# ATSAM3X8E_Main_Controller_-_TR_R1_1.net
KiCad netlist of a schematic drawn in Altium Designer
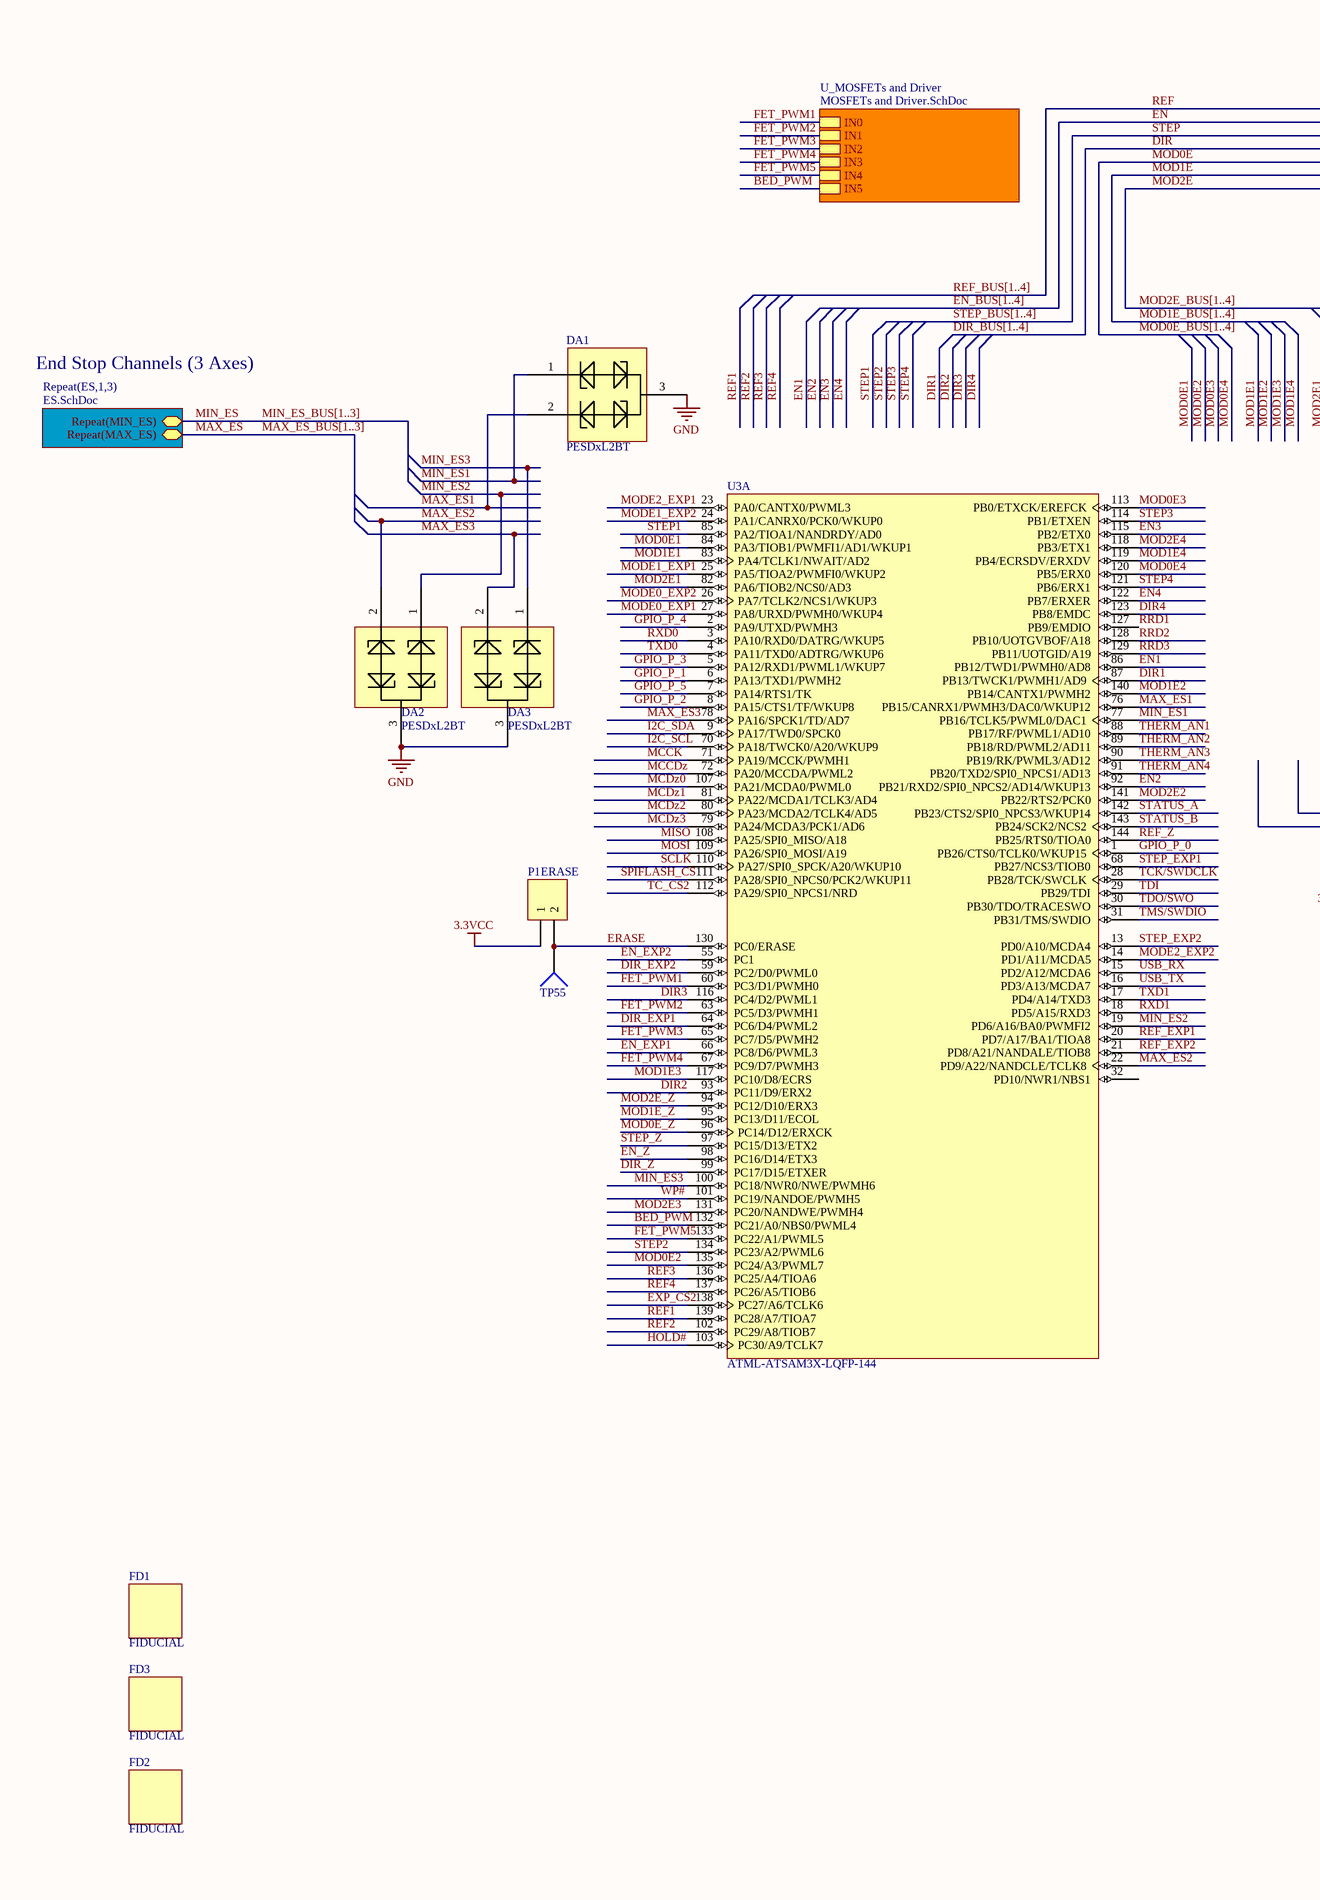
[diagram p0: ATSAM3X8E Main Controller - TR R1.1.SchDoc, left]
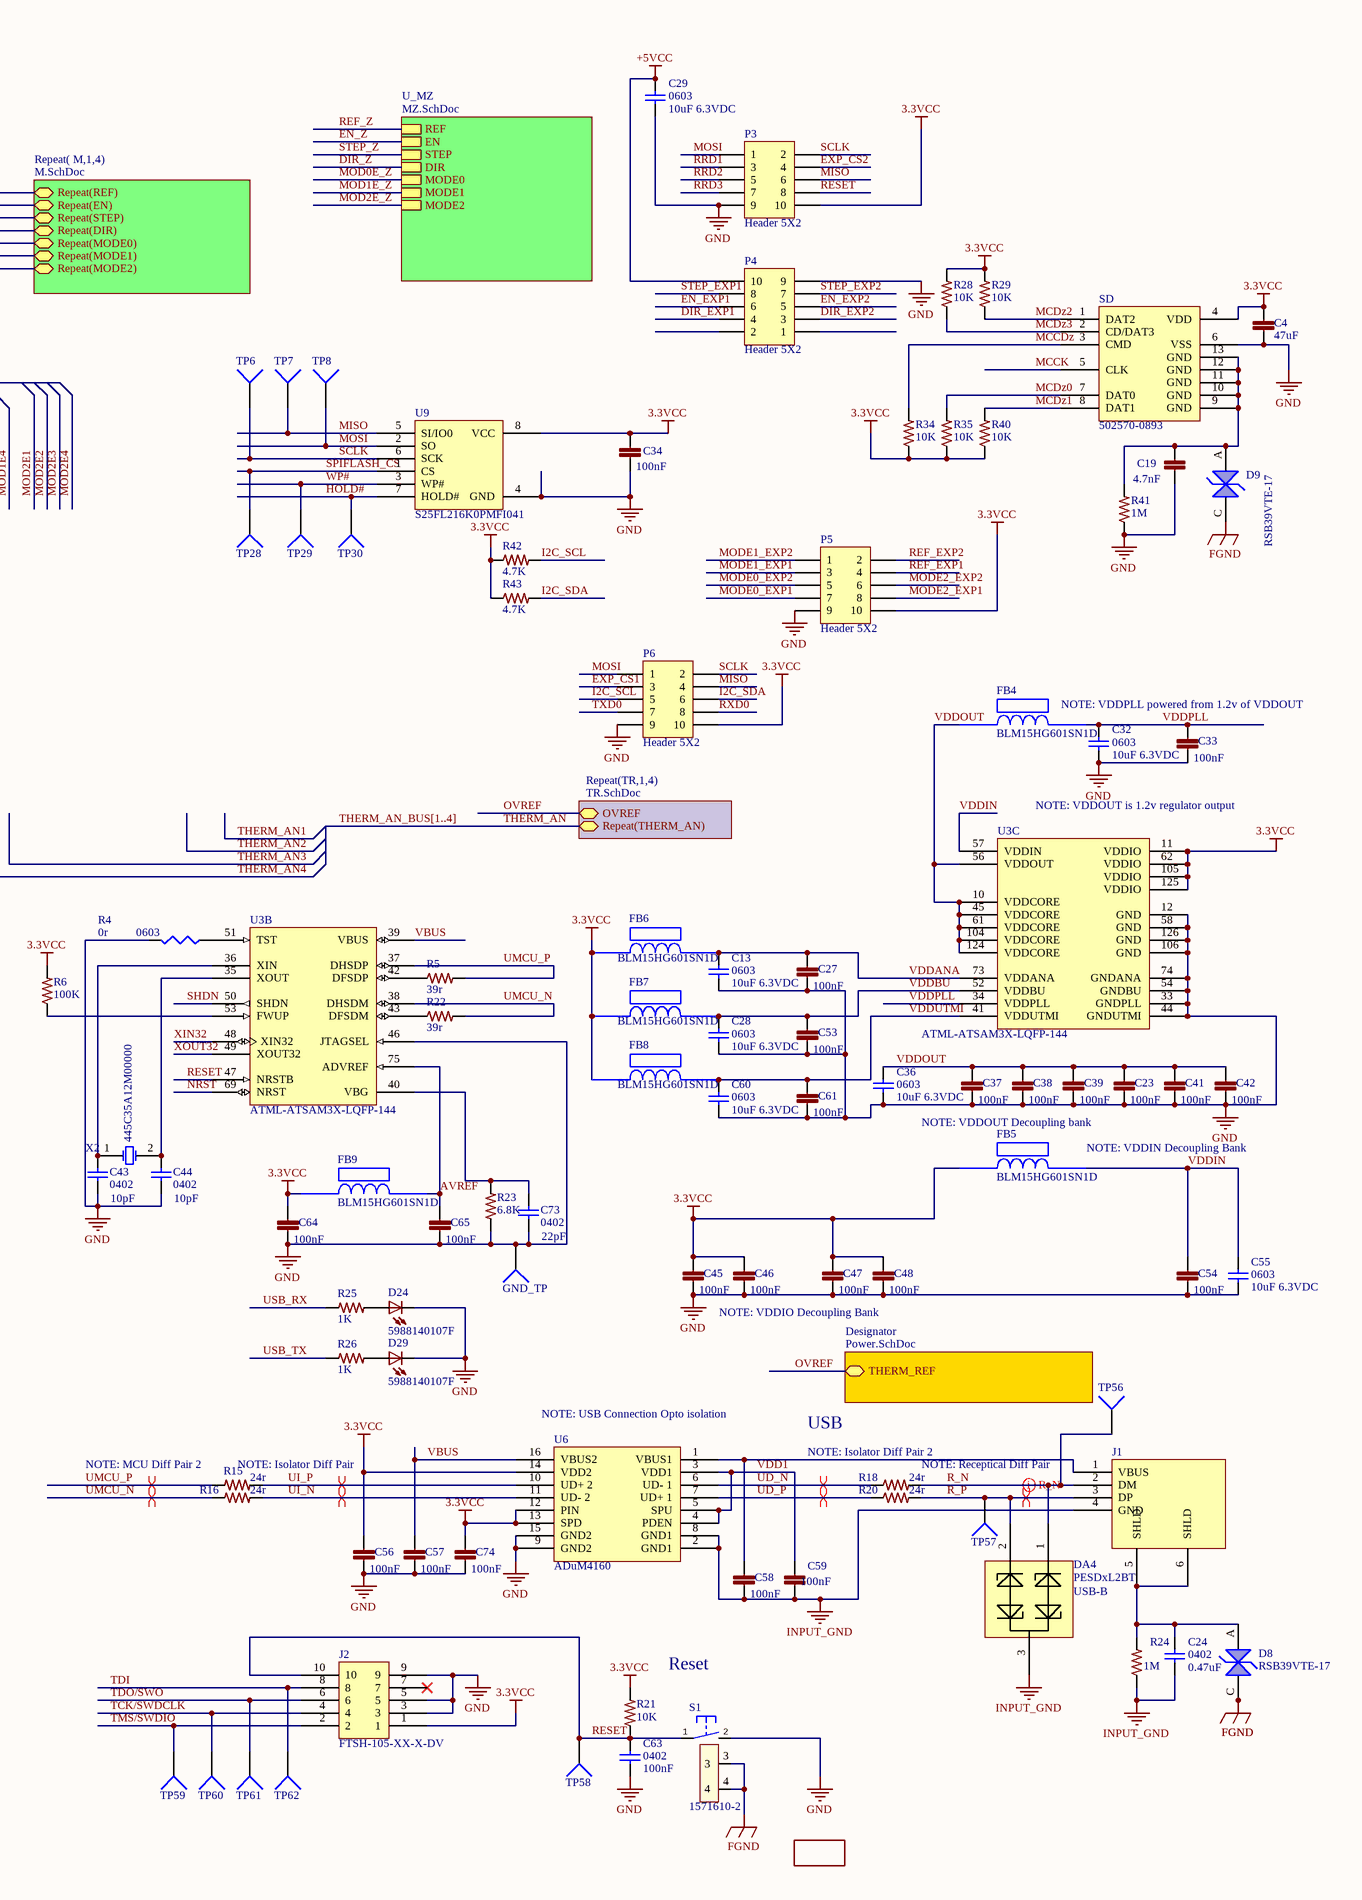
[diagram p1: ATSAM3X8E Main Controller - TR R1.1.SchDoc, right]

(export (version "E")
  (design (tool "Eeschema 10.0.6"))
  (components
    (comp (ref "C4")
      (value "47uF")
      (footprint "C0805")
      (description "CAP CER 47UF 6.3V 20% X5R 0805")
      (fields
        (field (name "MANUFACTURER") "Samsung")
        (field (name "MANUFACTURERPARTNUMBER") "CL21A476MQCLRNC")
        (field (name "PUBLISHER") "UltiMachine")
      )
      (libsource (lib "Tigershark3D") (part "CL21A476MQCLRNC"))
    )
    (comp (ref "C13")
      (value "0603")
      (footprint "C0603")
      (description "CAP CER 10UF 6.3V 10% JB 0603")
      (fields
        (field (name "MFR PART #") "C1608JB0J106K080AB")
        (field (name "MFR") "TDK")
        (field (name "ALTIUM_VALUE") "10uF 6.3VDC")
      )
      (libsource (lib "Tigershark3D") (part "C1608JB0J106K080AB"))
    )
    (comp (ref "C19")
      (value "4.7nF")
      (footprint "C0402")
      (description "CAP CER 0402 4.7nF 25V 10% X7R")
      (fields
        (field (name "MANUFACTURERPARTNUMBER") "CC0402KRX7R8BB472")
        (field (name "PUBLISHER") "UltiMachine")
      )
      (libsource (lib "3Delight") (part "CC0402KRX7R8BB472"))
    )
    (comp (ref "C23")
      (value "100nF")
      (footprint "C0402")
      (description "CAP CER 0402 100nF 16V 10% X7R")
      (fields
        (field (name "MANUFACTURERPARTNUMBER") "GRM155R71C104KA88D")
        (field (name "PUBLISHER") "UltiMachine")
      )
      (libsource (lib "3Delight") (part "GRM155R71C104KA88D"))
    )
    (comp (ref "C24")
      (value "0.47uF")
      (footprint "C0402")
      (description "0.47uF 6.3v C0402 - GRM155R60J474KE19D")
      (fields
        (field (name "MFR PART #") "GRM155R60J474KE19D")
        (field (name "MFR") "Murata")
        (field (name "PACKAGEREFERENCE") "0402")
        (field (name "PUBLISHER") "Ultimachine")
      )
      (libsource (lib "Tigershark3D") (part "GRM155R60J474KE19D"))
    )
    (comp (ref "C27")
      (value "100nF")
      (footprint "C0402")
      (description "CAP CER 0402 100nF 16V 10% X7R")
      (fields
        (field (name "MANUFACTURERPARTNUMBER") "GRM155R71C104KA88D")
        (field (name "PUBLISHER") "UltiMachine")
      )
      (libsource (lib "3Delight") (part "GRM155R71C104KA88D"))
    )
    (comp (ref "C28")
      (value "0603")
      (footprint "C0603")
      (description "CAP CER 10UF 6.3V 10% JB 0603")
      (fields
        (field (name "MFR PART #") "C1608JB0J106K080AB")
        (field (name "MFR") "TDK")
        (field (name "ALTIUM_VALUE") "10uF 6.3VDC")
      )
      (libsource (lib "Tigershark3D") (part "C1608JB0J106K080AB"))
    )
    (comp (ref "C29")
      (value "0603")
      (footprint "C0603")
      (description "CAP CER 10UF 6.3V 10% JB 0603")
      (fields
        (field (name "MFR PART #") "C1608JB0J106K080AB")
        (field (name "MFR") "TDK")
        (field (name "ALTIUM_VALUE") "10uF 6.3VDC")
      )
      (libsource (lib "Tigershark3D") (part "C1608JB0J106K080AB"))
    )
    (comp (ref "C32")
      (value "0603")
      (footprint "C0603")
      (description "CAP CER 10UF 6.3V 10% JB 0603")
      (fields
        (field (name "MFR PART #") "C1608JB0J106K080AB")
        (field (name "MFR") "TDK")
        (field (name "ALTIUM_VALUE") "10uF 6.3VDC")
      )
      (libsource (lib "Tigershark3D") (part "C1608JB0J106K080AB"))
    )
    (comp (ref "C33")
      (value "100nF")
      (footprint "C0402")
      (description "CAP CER 0402 100nF 16V 10% X7R")
      (fields
        (field (name "MANUFACTURERPARTNUMBER") "GRM155R71C104KA88D")
        (field (name "PUBLISHER") "UltiMachine")
      )
      (libsource (lib "3Delight") (part "GRM155R71C104KA88D"))
    )
    (comp (ref "C34")
      (value "100nF")
      (footprint "C0402")
      (description "CAP CER 0402 100nF 16V 10% X7R")
      (fields
        (field (name "MANUFACTURERPARTNUMBER") "GRM155R71C104KA88D")
        (field (name "PUBLISHER") "UltiMachine")
      )
      (libsource (lib "3Delight") (part "GRM155R71C104KA88D"))
    )
    (comp (ref "C36")
      (value "0603")
      (footprint "C0603")
      (description "CAP CER 10UF 6.3V 10% JB 0603")
      (fields
        (field (name "MFR PART #") "C1608JB0J106K080AB")
        (field (name "MFR") "TDK")
        (field (name "ALTIUM_VALUE") "10uF 6.3VDC")
      )
      (libsource (lib "Tigershark3D") (part "C1608JB0J106K080AB"))
    )
    (comp (ref "C37")
      (value "100nF")
      (footprint "C0402")
      (description "CAP CER 0402 100nF 16V 10% X7R")
      (fields
        (field (name "MANUFACTURERPARTNUMBER") "GRM155R71C104KA88D")
        (field (name "PUBLISHER") "UltiMachine")
      )
      (libsource (lib "3Delight") (part "GRM155R71C104KA88D"))
    )
    (comp (ref "C38")
      (value "100nF")
      (footprint "C0402")
      (description "CAP CER 0402 100nF 16V 10% X7R")
      (fields
        (field (name "MANUFACTURERPARTNUMBER") "GRM155R71C104KA88D")
        (field (name "PUBLISHER") "UltiMachine")
      )
      (libsource (lib "3Delight") (part "GRM155R71C104KA88D"))
    )
    (comp (ref "C39")
      (value "100nF")
      (footprint "C0402")
      (description "CAP CER 0402 100nF 16V 10% X7R")
      (fields
        (field (name "MANUFACTURERPARTNUMBER") "GRM155R71C104KA88D")
        (field (name "PUBLISHER") "UltiMachine")
      )
      (libsource (lib "3Delight") (part "GRM155R71C104KA88D"))
    )
    (comp (ref "C41")
      (value "100nF")
      (footprint "C0402")
      (description "CAP CER 0402 100nF 16V 10% X7R")
      (fields
        (field (name "MANUFACTURERPARTNUMBER") "GRM155R71C104KA88D")
        (field (name "PUBLISHER") "UltiMachine")
      )
      (libsource (lib "3Delight") (part "GRM155R71C104KA88D"))
    )
    (comp (ref "C42")
      (value "100nF")
      (footprint "C0402")
      (description "CAP CER 0402 100nF 16V 10% X7R")
      (fields
        (field (name "MANUFACTURERPARTNUMBER") "GRM155R71C104KA88D")
        (field (name "PUBLISHER") "UltiMachine")
      )
      (libsource (lib "3Delight") (part "GRM155R71C104KA88D"))
    )
    (comp (ref "C43")
      (value "0402")
      (footprint "C0402")
      (description "CAP CER 10PF 50V 5% NP0 0402")
      (fields
        (field (name "MFR PART #") "CL05C100JB5NNNC")
        (field (name "MFR") "Samsung")
        (field (name "ALTIUM_VALUE") "10pF")
        (field (name "PUBLISHER") "Ultimachine")
      )
      (libsource (lib "Tigershark3D") (part "CL05C100JB5NNNC"))
    )
    (comp (ref "C44")
      (value "0402")
      (footprint "C0402")
      (description "CAP CER 10PF 50V 5% NP0 0402")
      (fields
        (field (name "MFR PART #") "CL05C100JB5NNNC")
        (field (name "MFR") "Samsung")
        (field (name "ALTIUM_VALUE") "10pF")
        (field (name "PUBLISHER") "Ultimachine")
      )
      (libsource (lib "Tigershark3D") (part "CL05C100JB5NNNC"))
    )
    (comp (ref "C45")
      (value "100nF")
      (footprint "C0402")
      (description "CAP CER 0402 100nF 16V 10% X7R")
      (fields
        (field (name "MANUFACTURERPARTNUMBER") "GRM155R71C104KA88D")
        (field (name "PUBLISHER") "UltiMachine")
      )
      (libsource (lib "3Delight") (part "GRM155R71C104KA88D"))
    )
    (comp (ref "C46")
      (value "100nF")
      (footprint "C0402")
      (description "CAP CER 0402 100nF 16V 10% X7R")
      (fields
        (field (name "MANUFACTURERPARTNUMBER") "GRM155R71C104KA88D")
        (field (name "PUBLISHER") "UltiMachine")
      )
      (libsource (lib "3Delight") (part "GRM155R71C104KA88D"))
    )
    (comp (ref "C47")
      (value "100nF")
      (footprint "C0402")
      (description "CAP CER 0402 100nF 16V 10% X7R")
      (fields
        (field (name "MANUFACTURERPARTNUMBER") "GRM155R71C104KA88D")
        (field (name "PUBLISHER") "UltiMachine")
      )
      (libsource (lib "3Delight") (part "GRM155R71C104KA88D"))
    )
    (comp (ref "C48")
      (value "100nF")
      (footprint "C0402")
      (description "CAP CER 0402 100nF 16V 10% X7R")
      (fields
        (field (name "MANUFACTURERPARTNUMBER") "GRM155R71C104KA88D")
        (field (name "PUBLISHER") "UltiMachine")
      )
      (libsource (lib "3Delight") (part "GRM155R71C104KA88D"))
    )
    (comp (ref "C53")
      (value "100nF")
      (footprint "C0402")
      (description "CAP CER 0402 100nF 16V 10% X7R")
      (fields
        (field (name "MANUFACTURERPARTNUMBER") "GRM155R71C104KA88D")
        (field (name "PUBLISHER") "UltiMachine")
      )
      (libsource (lib "3Delight") (part "GRM155R71C104KA88D"))
    )
    (comp (ref "C54")
      (value "100nF")
      (footprint "C0402")
      (description "CAP CER 0402 100nF 16V 10% X7R")
      (fields
        (field (name "MANUFACTURERPARTNUMBER") "GRM155R71C104KA88D")
        (field (name "PUBLISHER") "UltiMachine")
      )
      (libsource (lib "3Delight") (part "GRM155R71C104KA88D"))
    )
    (comp (ref "C55")
      (value "0603")
      (footprint "C0603")
      (description "CAP CER 10UF 6.3V 10% JB 0603")
      (fields
        (field (name "MFR PART #") "C1608JB0J106K080AB")
        (field (name "MFR") "TDK")
        (field (name "ALTIUM_VALUE") "10uF 6.3VDC")
      )
      (libsource (lib "Tigershark3D") (part "C1608JB0J106K080AB"))
    )
    (comp (ref "C56")
      (value "100nF")
      (footprint "C0402")
      (description "CAP CER 0402 100nF 16V 10% X7R")
      (fields
        (field (name "MANUFACTURERPARTNUMBER") "GRM155R71C104KA88D")
        (field (name "PUBLISHER") "UltiMachine")
      )
      (libsource (lib "3Delight") (part "GRM155R71C104KA88D"))
    )
    (comp (ref "C57")
      (value "100nF")
      (footprint "C0402")
      (description "CAP CER 0402 100nF 16V 10% X7R")
      (fields
        (field (name "MANUFACTURERPARTNUMBER") "GRM155R71C104KA88D")
        (field (name "PUBLISHER") "UltiMachine")
      )
      (libsource (lib "3Delight") (part "GRM155R71C104KA88D"))
    )
    (comp (ref "C58")
      (value "100nF")
      (footprint "C0402")
      (description "CAP CER 0402 100nF 16V 10% X7R")
      (fields
        (field (name "MANUFACTURERPARTNUMBER") "GRM155R71C104KA88D")
        (field (name "PUBLISHER") "UltiMachine")
      )
      (libsource (lib "3Delight") (part "GRM155R71C104KA88D"))
    )
    (comp (ref "C59")
      (value "100nF")
      (footprint "C0402")
      (description "CAP CER 0402 100nF 16V 10% X7R")
      (fields
        (field (name "MANUFACTURERPARTNUMBER") "GRM155R71C104KA88D")
        (field (name "PUBLISHER") "UltiMachine")
      )
      (libsource (lib "3Delight") (part "GRM155R71C104KA88D"))
    )
    (comp (ref "C60")
      (value "0603")
      (footprint "C0603")
      (description "CAP CER 10UF 6.3V 10% JB 0603")
      (fields
        (field (name "MFR PART #") "C1608JB0J106K080AB")
        (field (name "MFR") "TDK")
        (field (name "ALTIUM_VALUE") "10uF 6.3VDC")
      )
      (libsource (lib "Tigershark3D") (part "C1608JB0J106K080AB"))
    )
    (comp (ref "C61")
      (value "100nF")
      (footprint "C0402")
      (description "CAP CER 0402 100nF 16V 10% X7R")
      (fields
        (field (name "MANUFACTURERPARTNUMBER") "GRM155R71C104KA88D")
        (field (name "PUBLISHER") "UltiMachine")
      )
      (libsource (lib "3Delight") (part "GRM155R71C104KA88D"))
    )
    (comp (ref "C63")
      (value "100nF")
      (footprint "C0402")
      (description "Capacitor (Semiconductor SIM Model)")
      (fields
        (field (name "MFR PART #") "GRM155R71C104KA88D")
        (field (name "MFR") "Murata")
        (field (name "PACKAGEREFERENCE") "0402")
        (field (name "PUBLISHER") "Ultimachine")
      )
      (libsource (lib "Tigershark3D") (part "100nF C0402 - GRM155R71C104KA88D"))
    )
    (comp (ref "C64")
      (value "100nF")
      (footprint "C0402")
      (description "CAP CER 0402 100nF 16V 10% X7R")
      (fields
        (field (name "MANUFACTURERPARTNUMBER") "GRM155R71C104KA88D")
        (field (name "PUBLISHER") "UltiMachine")
      )
      (libsource (lib "3Delight") (part "GRM155R71C104KA88D"))
    )
    (comp (ref "C65")
      (value "100nF")
      (footprint "C0402")
      (description "CAP CER 0402 100nF 16V 10% X7R")
      (fields
        (field (name "MANUFACTURERPARTNUMBER") "GRM155R71C104KA88D")
        (field (name "PUBLISHER") "UltiMachine")
      )
      (libsource (lib "3Delight") (part "GRM155R71C104KA88D"))
    )
    (comp (ref "C73")
      (value "0402")
      (footprint "C0402")
      (description "CAP CER 22PF 50V 5% NP0 0402")
      (fields
        (field (name "MFR PART #") "CL05C220JB5NNNC")
        (field (name "MFR") "Samsung")
        (field (name "ALTIUM_VALUE") "22pF")
        (field (name "PUBLISHER") "Ultimachine")
      )
      (libsource (lib "Tigershark3D") (part "CL05C220JB5NNNC"))
    )
    (comp (ref "C74")
      (value "100nF")
      (footprint "C0402")
      (description "CAP CER 0402 100nF 16V 10% X7R")
      (fields
        (field (name "MANUFACTURERPARTNUMBER") "GRM155R71C104KA88D")
        (field (name "PUBLISHER") "UltiMachine")
      )
      (libsource (lib "3Delight") (part "GRM155R71C104KA88D"))
    )
    (comp (ref "D8")
      (value "RSB39VTE-17")
      (footprint "SOD323-R")
      (description "DIODE TVS")
      (libsource (lib "Tigershark3D") (part "RSB39VTE-17"))
    )
    (comp (ref "D9")
      (value "RSB39VTE-17")
      (footprint "SOD323-R")
      (description "DIODE TVS")
      (libsource (lib "3Delight") (part "RSB39VTE-17"))
    )
    (comp (ref "D24")
      (value "5988140107F")
      (footprint "LED2012120")
      (description "LED 0805 Yellow")
      (fields (field (name "PUBLISHER") "UltiMachine"))
      (libsource (lib "Tigershark3D") (part "5988140107F"))
    )
    (comp (ref "D29")
      (value "5988140107F")
      (footprint "LED2012120")
      (description "LED 0805 Yellow")
      (fields (field (name "PUBLISHER") "UltiMachine"))
      (libsource (lib "Tigershark3D") (part "5988140107F"))
    )
    (comp (ref "DA1")
      (value "PESDxL2BT")
      (footprint "SOT95P230X110-3N")
      (description "PESDxL2BT TVS Diode Array 2x")
      (libsource (lib "") (part "PESDxL2BT_1"))
    )
    (comp (ref "DA2")
      (value "PESDxL2BT")
      (footprint "SOT95P230X110-3N")
      (description "PESDxL2BT TVS Diode Array 2x")
      (libsource (lib "ZMBo Schematic Library") (part "PESDxL2BT"))
    )
    (comp (ref "DA3")
      (value "PESDxL2BT")
      (footprint "SOT95P230X110-3N")
      (description "PESDxL2BT TVS Diode Array 2x")
      (libsource (lib "ZMBo Schematic Library") (part "PESDxL2BT"))
    )
    (comp (ref "DA4")
      (value "PESDxL2BT")
      (footprint "SOT95P230X110-3N")
      (description "PESDxL2BT TVS Diode Array 2x")
      (libsource (lib "ZMBo Schematic Library") (part "PESDxL2BT"))
    )
    (comp (ref "FB4")
      (value "BLM15HG601SN1D")
      (footprint "BLM18PG121SN1D")
      (libsource (lib "AHD Part Library") (part "BLM15HG601SN1D"))
    )
    (comp (ref "FB5")
      (value "BLM15HG601SN1D")
      (footprint "BLM18PG121SN1D")
      (libsource (lib "AHD Part Library") (part "BLM15HG601SN1D"))
    )
    (comp (ref "FB6")
      (value "BLM15HG601SN1D")
      (footprint "BLM18PG121SN1D")
      (libsource (lib "AHD Part Library") (part "BLM15HG601SN1D"))
    )
    (comp (ref "FB7")
      (value "BLM15HG601SN1D")
      (footprint "BLM18PG121SN1D")
      (libsource (lib "AHD Part Library") (part "BLM15HG601SN1D"))
    )
    (comp (ref "FB8")
      (value "BLM15HG601SN1D")
      (footprint "BLM18PG121SN1D")
      (libsource (lib "AHD Part Library") (part "BLM15HG601SN1D"))
    )
    (comp (ref "FB9")
      (value "BLM15HG601SN1D")
      (footprint "BLM18PG121SN1D")
      (libsource (lib "AHD Part Library") (part "BLM15HG601SN1D"))
    )
    (comp (ref "FD1")
      (value "FIDUCIAL")
      (footprint "FIDUCIAL-1X2")
      (libsource (lib "ZMBo Schematic Library") (part "FIDUCIAL"))
    )
    (comp (ref "FD2")
      (value "FIDUCIAL")
      (footprint "FIDUCIAL-1X2")
      (libsource (lib "ZMBo Schematic Library") (part "FIDUCIAL"))
    )
    (comp (ref "FD3")
      (value "FIDUCIAL")
      (footprint "FIDUCIAL-1X2")
      (libsource (lib "ZMBo Schematic Library") (part "FIDUCIAL"))
    )
    (comp (ref "GND_TP")
      (value "TP4")
      (footprint "TP-2")
      (description "Socket")
      (fields (field (name "PUBLISHER") "Altium Limited"))
      (libsource (lib "ZMBo Schematic Library") (part "Socket"))
    )
    (comp (ref "J1")
      (value "USB-B")
      (footprint "PN61729")
      (libsource (lib "ZMBo Schematic Library") (part "USB-B"))
    )
    (comp (ref "J2")
      (value "FTSH-105-XX-X-DV")
      (footprint "FTSH-105-XX-X-DV")
      (libsource (lib "Adams Altium Library") (part "ARM Cortex JTAG-DEBUG Header"))
    )
    (comp (ref "LOGO1")
      (value "OSHW_LOGO_8MILX0150-NT")
      (footprint "OSHW_8X150_NOTEXT")
      (fields (field (name "PUBLISHER") "UltiMachine"))
      (libsource (lib "3Delight") (part "OSHW_LOGO_8MILX0150-NT"))
    )
    (comp (ref "P1")
      (value "ERASE")
      (footprint "HDR1X2")
      (description "Header, 2-Pin")
      (fields (field (name "PUBLISHER") "Altium Limited"))
      (libsource (lib "Miscellaneous Connectors") (part "Header 2"))
    )
    (comp (ref "P3")
      (value "Header 5X2")
      (footprint "HDR2X5")
      (description "Header, 5-Pin, Dual row")
      (fields (field (name "PUBLISHER") "Altium Limited"))
      (libsource (lib "Miscellaneous Connectors") (part "Header 5X2"))
    )
    (comp (ref "P4")
      (value "Header 5X2")
      (footprint "HDR2X5")
      (description "Header, 5-Pin, Dual row")
      (fields (field (name "PUBLISHER") "Altium Limited"))
      (libsource (lib "") (part "Header 5X2_1"))
    )
    (comp (ref "P5")
      (value "Header 5X2")
      (footprint "HDR2X5")
      (description "Header, 5-Pin, Dual row")
      (fields (field (name "PUBLISHER") "Altium Limited"))
      (libsource (lib "Miscellaneous Connectors") (part "Header 5X2"))
    )
    (comp (ref "P6")
      (value "Header 5X2")
      (footprint "HDR2X5")
      (description "Header, 5-Pin, Dual row")
      (fields (field (name "PUBLISHER") "Altium Limited"))
      (libsource (lib "Miscellaneous Connectors") (part "Header 5X2"))
    )
    (comp (ref "R4")
      (value "0603")
      (footprint "J1-0603")
      (description "Resistor")
      (fields (field (name "ALTIUM_VALUE") "0r") (field (name "PUBLISHER") "Altium Limited"))
      (libsource (lib "Miscellaneous Devices") (part "Res3"))
    )
    (comp (ref "R5")
      (value "39r")
      (footprint "R0402")
      (description "RES SMD 39 OHM 1% 1/10W 0402")
      (fields
        (field (name "MANUFACTURER") "Panasonic")
        (field (name "MANUFACTURERPARTNUMBER") "ERJ-2RKF39R0X")
        (field (name "PUBLISHER") "UltiMachine")
      )
      (libsource (lib "Tigershark3D") (part "ERJ-2RKF39R0X"))
    )
    (comp (ref "R6")
      (value "100K")
      (footprint "R0603")
      (description "RES 100K OHM 1/10W 1% 0603 SMD")
      (fields
        (field (name "MANUFACTURERPARTNUMBER") "RC0603FR-07100KL")
        (field (name "PUBLISHER") "UltiMachine")
      )
      (libsource (lib "Tigershark3D") (part "RC0603FR-07100KL"))
    )
    (comp (ref "R15")
      (value "24r")
      (footprint "R0603")
      (description "RES SMD 24 OHM 1% 1/10W 0603")
      (fields
        (field (name "MANUFACTURER") "Samsung")
        (field (name "MANUFACTURERPARTNUMBER") "RC0603FR-07100KL")
        (field (name "PUBLISHER") "UltiMachine")
      )
      (libsource (lib "Tigershark3D") (part "RC1608F240CS"))
    )
    (comp (ref "R16")
      (value "24r")
      (footprint "R0603")
      (description "RES SMD 24 OHM 1% 1/10W 0603")
      (fields
        (field (name "MANUFACTURER") "Samsung")
        (field (name "MANUFACTURERPARTNUMBER") "RC0603FR-07100KL")
        (field (name "PUBLISHER") "UltiMachine")
      )
      (libsource (lib "Tigershark3D") (part "RC1608F240CS"))
    )
    (comp (ref "R18")
      (value "24r")
      (footprint "R0603")
      (description "RES SMD 24 OHM 1% 1/10W 0603")
      (fields
        (field (name "MANUFACTURER") "Samsung")
        (field (name "MANUFACTURERPARTNUMBER") "RC0603FR-07100KL")
        (field (name "PUBLISHER") "UltiMachine")
      )
      (libsource (lib "Tigershark3D") (part "RC1608F240CS"))
    )
    (comp (ref "R20")
      (value "24r")
      (footprint "R0603")
      (description "RES SMD 24 OHM 1% 1/10W 0603")
      (fields
        (field (name "MANUFACTURER") "Samsung")
        (field (name "MANUFACTURERPARTNUMBER") "RC0603FR-07100KL")
        (field (name "PUBLISHER") "UltiMachine")
      )
      (libsource (lib "Tigershark3D") (part "RC1608F240CS"))
    )
    (comp (ref "R21")
      (value "10K")
      (footprint "R0603")
      (description "RES 0603 10K 100mW 1%")
      (fields
        (field (name "MANUFACTURERPARTNUMBER") "ERJ-3EKF1002V")
        (field (name "PUBLISHER") "UltiMachine")
      )
      (libsource (lib "3Delight") (part "ERJ-3EKF1002V"))
    )
    (comp (ref "R22")
      (value "39r")
      (footprint "R0402")
      (description "RES SMD 39 OHM 1% 1/10W 0402")
      (fields
        (field (name "MANUFACTURER") "Panasonic")
        (field (name "MANUFACTURERPARTNUMBER") "ERJ-2RKF39R0X")
        (field (name "PUBLISHER") "UltiMachine")
      )
      (libsource (lib "Tigershark3D") (part "ERJ-2RKF39R0X"))
    )
    (comp (ref "R23")
      (value "6.8K")
      (footprint "R0402")
      (description "RES SMD 6.8K OHM 1% 1/16W 0402")
      (fields
        (field (name "MANUFACTURER") "Vishay Dale")
        (field (name "MANUFACTURERPARTNUMBER") "CRCW04026K80FKED")
        (field (name "PUBLISHER") "UltiMachine")
      )
      (libsource (lib "Tigershark3D") (part "CRCW04026K80FKED"))
    )
    (comp (ref "R24")
      (value "1M")
      (footprint "R0402")
      (description "RES 0402 1M 100mW 5%")
      (fields (field (name "MANUFACTURERPARTNUMBER") "ERJ2GEJ105X") (field (name "PUBLISHER") "UltiMachine"))
      (libsource (lib "Tigershark3D") (part "ERJ2GEJ105X"))
    )
    (comp (ref "R25")
      (value "1K")
      (footprint "R0603")
      (description "RES 0603 1K 100mW 1%")
      (fields
        (field (name "MANUFACTURERPARTNUMBER") "ERJ-3EKF1001V")
        (field (name "PUBLISHER") "UltiMachine")
      )
      (libsource (lib "Tigershark3D") (part "ERJ-3EKF1001V"))
    )
    (comp (ref "R26")
      (value "1K")
      (footprint "R0603")
      (description "RES 0603 1K 100mW 1%")
      (fields
        (field (name "MANUFACTURERPARTNUMBER") "ERJ-3EKF1001V")
        (field (name "PUBLISHER") "UltiMachine")
      )
      (libsource (lib "Tigershark3D") (part "ERJ-3EKF1001V"))
    )
    (comp (ref "R28")
      (value "10K")
      (footprint "R0603")
      (description "RES 0603 10K 100mW 1%")
      (fields
        (field (name "MANUFACTURERPARTNUMBER") "ERJ-3EKF1002V")
        (field (name "PUBLISHER") "UltiMachine")
      )
      (libsource (lib "Tigershark3D") (part "ERJ-3EKF1002V"))
    )
    (comp (ref "R29")
      (value "10K")
      (footprint "R0603")
      (description "RES 0603 10K 100mW 1%")
      (fields
        (field (name "MANUFACTURERPARTNUMBER") "ERJ-3EKF1002V")
        (field (name "PUBLISHER") "UltiMachine")
      )
      (libsource (lib "Tigershark3D") (part "ERJ-3EKF1002V"))
    )
    (comp (ref "R34")
      (value "10K")
      (footprint "R0603")
      (description "RES 0603 10K 100mW 1%")
      (fields
        (field (name "MANUFACTURERPARTNUMBER") "ERJ-3EKF1002V")
        (field (name "PUBLISHER") "UltiMachine")
      )
      (libsource (lib "Tigershark3D") (part "ERJ-3EKF1002V"))
    )
    (comp (ref "R35")
      (value "10K")
      (footprint "R0603")
      (description "RES 0603 10K 100mW 1%")
      (fields
        (field (name "MANUFACTURERPARTNUMBER") "ERJ-3EKF1002V")
        (field (name "PUBLISHER") "UltiMachine")
      )
      (libsource (lib "Tigershark3D") (part "ERJ-3EKF1002V"))
    )
    (comp (ref "R40")
      (value "10K")
      (footprint "R0603")
      (description "RES 0603 10K 100mW 1%")
      (fields
        (field (name "MANUFACTURERPARTNUMBER") "ERJ-3EKF1002V")
        (field (name "PUBLISHER") "UltiMachine")
      )
      (libsource (lib "Tigershark3D") (part "ERJ-3EKF1002V"))
    )
    (comp (ref "R41")
      (value "1M")
      (footprint "R0402")
      (description "RES 0402 1M 100mW 5%")
      (fields (field (name "MANUFACTURERPARTNUMBER") "ERJ2GEJ105X") (field (name "PUBLISHER") "UltiMachine"))
      (libsource (lib "3Delight") (part "ERJ2GEJ105X"))
    )
    (comp (ref "R42")
      (value "4.7K")
      (footprint "R0603")
      (description "RES 0603 4.7K 100mW 1%")
      (fields (field (name "MANUFACTURERPARTNUMBER") "ERJ3EKF4701V") (field (name "PUBLISHER") "UltiMachine"))
      (libsource (lib "Tigershark3D") (part "ERJ3EKF4701V"))
    )
    (comp (ref "R43")
      (value "4.7K")
      (footprint "R0603")
      (description "RES 0603 4.7K 100mW 1%")
      (fields (field (name "MANUFACTURERPARTNUMBER") "ERJ3EKF4701V") (field (name "PUBLISHER") "UltiMachine"))
      (libsource (lib "Tigershark3D") (part "ERJ3EKF4701V"))
    )
    (comp (ref "S1")
      (value "1571610-2")
      (footprint "B3F-31XX")
      (description "SWTCH Momentary Washable")
      (fields
        (field (name "MANUFACTURER") "Omron")
        (field (name "MANUFACTURER_1") "TE")
        (field (name "PUBLISHER") "UltiMachine")
      )
      (libsource (lib "ZMBo Schematic Library") (part "1571610-2_1"))
    )
    (comp (ref "SD")
      (value "502570-0893")
      (footprint "502570-0893 - Molex SD")
      (description "microSD 502570-0893 Molex Part")
      (libsource (lib "Tigershark3D") (part "502570-0893"))
    )
    (comp (ref "TP6")
      (value "TP4")
      (footprint "TP-2")
      (description "Socket")
      (fields (field (name "PUBLISHER") "Altium Limited"))
      (libsource (lib "ZMBo Schematic Library") (part "Socket"))
    )
    (comp (ref "TP7")
      (value "TP4")
      (footprint "TP-2")
      (description "Socket")
      (fields (field (name "PUBLISHER") "Altium Limited"))
      (libsource (lib "ZMBo Schematic Library") (part "Socket"))
    )
    (comp (ref "TP8")
      (value "TP4")
      (footprint "TP-2")
      (description "Socket")
      (fields (field (name "PUBLISHER") "Altium Limited"))
      (libsource (lib "ZMBo Schematic Library") (part "Socket"))
    )
    (comp (ref "TP28")
      (value "TP4")
      (footprint "TP-2")
      (description "Socket")
      (fields (field (name "PUBLISHER") "Altium Limited"))
      (libsource (lib "ZMBo Schematic Library") (part "Socket"))
    )
    (comp (ref "TP29")
      (value "TP4")
      (footprint "TP-2")
      (description "Socket")
      (fields (field (name "PUBLISHER") "Altium Limited"))
      (libsource (lib "ZMBo Schematic Library") (part "Socket"))
    )
    (comp (ref "TP30")
      (value "TP4")
      (footprint "TP-2")
      (description "Socket")
      (fields (field (name "PUBLISHER") "Altium Limited"))
      (libsource (lib "ZMBo Schematic Library") (part "Socket"))
    )
    (comp (ref "TP55")
      (value "TP4")
      (footprint "TP-2")
      (description "Socket")
      (fields (field (name "PUBLISHER") "Altium Limited"))
      (libsource (lib "ZMBo Schematic Library") (part "Socket"))
    )
    (comp (ref "TP56")
      (value "TP4")
      (footprint "TP-2")
      (description "Socket")
      (fields (field (name "PUBLISHER") "Altium Limited"))
      (libsource (lib "ZMBo Schematic Library") (part "Socket"))
    )
    (comp (ref "TP57")
      (value "TP4")
      (footprint "TP-2")
      (description "Socket")
      (fields (field (name "PUBLISHER") "Altium Limited"))
      (libsource (lib "ZMBo Schematic Library") (part "Socket"))
    )
    (comp (ref "TP58")
      (value "TP4")
      (footprint "TP-2")
      (description "Socket")
      (fields (field (name "PUBLISHER") "Altium Limited"))
      (libsource (lib "ZMBo Schematic Library") (part "Socket"))
    )
    (comp (ref "TP59")
      (value "TP4")
      (footprint "TP-2")
      (description "Socket")
      (fields (field (name "PUBLISHER") "Altium Limited"))
      (libsource (lib "ZMBo Schematic Library") (part "Socket"))
    )
    (comp (ref "TP60")
      (value "TP4")
      (footprint "TP-2")
      (description "Socket")
      (fields (field (name "PUBLISHER") "Altium Limited"))
      (libsource (lib "ZMBo Schematic Library") (part "Socket"))
    )
    (comp (ref "TP61")
      (value "TP4")
      (footprint "TP-2")
      (description "Socket")
      (fields (field (name "PUBLISHER") "Altium Limited"))
      (libsource (lib "ZMBo Schematic Library") (part "Socket"))
    )
    (comp (ref "TP62")
      (value "TP4")
      (footprint "TP-2")
      (description "Socket")
      (fields (field (name "PUBLISHER") "Altium Limited"))
      (libsource (lib "ZMBo Schematic Library") (part "Socket"))
    )
    (comp (ref "U3")
      (value "ATML-ATSAM3X-LQFP-144")
      (footprint "LQFP144_N")
      (libsource (lib "ZMBo Schematic Library") (part "ATML-ATSAM3X-LQFP-144"))
    )
    (comp (ref "U6")
      (value "ADuM4160")
      (footprint "ADuM4160")
      (description "USB Opto Isolator")
      (libsource (lib "ZMBo Schematic Library") (part "ADuM4160"))
    )
    (comp (ref "U9")
      (value "S25FL216K0PMFI041")
      (footprint "S25FL216K0PMFI041")
      (fields (field (name "DIGIKEY PART NUMBER") "1274-1052-ND"))
      (libsource (lib "Tigershark3D") (part "S25FL216K0PMFI041"))
    )
    (comp (ref "X2")
      (value "445C35A12M00000")
      (footprint "445C35A12M00000")
      (description "Crystal Oscillator")
      (fields (field (name "PUBLISHER") "Altium Limited"))
      (libsource (lib "Miscellaneous Devices") (part "XTAL"))
    )
  )
  (nets
    (net (code "39") (name "+5VCC") (class "Default")
      (node (ref "C29") (pin "2") (pinfunction "2_2") (pintype "passive"))
      (node (ref "P4") (pin "10") (pinfunction "10_10") (pintype "passive"))
    )
    (net (code "40") (name "/AVREF") (class "Default")
      (node (ref "C65") (pin "1") (pinfunction "1_1") (pintype "passive"))
      (node (ref "FB9") (pin "2") (pinfunction "2_2") (pintype "passive"))
      (node (ref "U3") (pin "75") (pinfunction "ADVREF_75") (pintype "input"))
    )
    (net (code "41") (name "/BED_PWM") (class "Default")
      (node (ref "U3") (pin "132") (pinfunction "PC21/A0/NBS0/PWML4_132") (pintype "bidirectional"))
    )
    (net (code "43") (name "/DIR1") (class "Default")
      (node (ref "U3") (pin "87") (pinfunction "PB13/TWCK1/PWMH1/AD9_87") (pintype "bidirectional"))
    )
    (net (code "44") (name "/DIR2") (class "Default")
      (node (ref "U3") (pin "93") (pinfunction "PC11/D9/ERX2_93") (pintype "bidirectional"))
    )
    (net (code "45") (name "/DIR3") (class "Default")
      (node (ref "U3") (pin "116") (pinfunction "PC4/D2/PWML1_116") (pintype "bidirectional"))
    )
    (net (code "46") (name "/DIR4") (class "Default")
      (node (ref "U3") (pin "123") (pinfunction "PB8/EMDC_123") (pintype "bidirectional"))
    )
    (net (code "48") (name "/DIR_EXP1") (class "Default")
      (node (ref "P4") (pin "4") (pinfunction "4_4") (pintype "passive"))
      (node (ref "U3") (pin "64") (pinfunction "PC6/D4/PWML2_64") (pintype "bidirectional"))
    )
    (net (code "49") (name "/DIR_EXP2") (class "Default")
      (node (ref "P4") (pin "3") (pinfunction "3_3") (pintype "passive"))
      (node (ref "U3") (pin "59") (pinfunction "PC2/D0/PWML0_59") (pintype "bidirectional"))
    )
    (net (code "50") (name "/DIR_Z") (class "Default")
      (node (ref "U3") (pin "99") (pinfunction "PC17/D15/ETXER_99") (pintype "bidirectional"))
    )
    (net (code "52") (name "/EN1") (class "Default")
      (node (ref "U3") (pin "86") (pinfunction "PB12/TWD1/PWMH0/AD8_86") (pintype "bidirectional"))
    )
    (net (code "53") (name "/EN2") (class "Default")
      (node (ref "U3") (pin "92") (pinfunction "PB21/RXD2/SPI0_NPCS2/AD14/WKUP13_92") (pintype "bidirectional"))
    )
    (net (code "54") (name "/EN3") (class "Default")
      (node (ref "U3") (pin "115") (pinfunction "PB2/ETX0_115") (pintype "bidirectional"))
    )
    (net (code "55") (name "/EN4") (class "Default")
      (node (ref "U3") (pin "122") (pinfunction "PB7/ERXER_122") (pintype "bidirectional"))
    )
    (net (code "57") (name "/EN_EXP1") (class "Default")
      (node (ref "P4") (pin "6") (pinfunction "6_6") (pintype "passive"))
      (node (ref "U3") (pin "66") (pinfunction "PC8/D6/PWML3_66") (pintype "bidirectional"))
    )
    (net (code "58") (name "/EN_EXP2") (class "Default")
      (node (ref "P4") (pin "5") (pinfunction "5_5") (pintype "passive"))
      (node (ref "U3") (pin "55") (pinfunction "PC1_55") (pintype "bidirectional"))
    )
    (net (code "59") (name "/EN_Z") (class "Default")
      (node (ref "U3") (pin "98") (pinfunction "PC16/D14/ETX3_98") (pintype "bidirectional"))
    )
    (net (code "60") (name "/ERASE") (class "Default")
      (node (ref "P1") (pin "2") (pinfunction "2_2") (pintype "passive"))
      (node (ref "TP55") (pin "1") (pinfunction "1_1") (pintype "passive"))
      (node (ref "U3") (pin "130") (pinfunction "PC0/ERASE_130") (pintype "bidirectional"))
    )
    (net (code "61") (name "/EXP_CS1") (class "Default")
      (node (ref "P6") (pin "3") (pinfunction "3_3") (pintype "passive"))
    )
    (net (code "62") (name "/EXP_CS2") (class "Default")
      (node (ref "P3") (pin "4") (pinfunction "4_4") (pintype "passive"))
      (node (ref "U3") (pin "138") (pinfunction "PC27/A6/TCLK6_138") (pintype "bidirectional"))
    )
    (net (code "63") (name "/FET_PWM1") (class "Default")
      (node (ref "U3") (pin "60") (pinfunction "PC3/D1/PWMH0_60") (pintype "bidirectional"))
    )
    (net (code "64") (name "/FET_PWM2") (class "Default")
      (node (ref "U3") (pin "63") (pinfunction "PC5/D3/PWMH1_63") (pintype "bidirectional"))
    )
    (net (code "65") (name "/FET_PWM3") (class "Default")
      (node (ref "U3") (pin "65") (pinfunction "PC7/D5/PWMH2_65") (pintype "bidirectional"))
    )
    (net (code "66") (name "/FET_PWM4") (class "Default")
      (node (ref "U3") (pin "67") (pinfunction "PC9/D7/PWMH3_67") (pintype "bidirectional"))
    )
    (net (code "67") (name "/FET_PWM5") (class "Default")
      (node (ref "U3") (pin "133") (pinfunction "PC22/A1/PWML5_133") (pintype "bidirectional"))
    )
    (net (code "68") (name "/GPIO_P_0") (class "Default")
      (node (ref "U3") (pin "1") (pinfunction "PB26/CTS0/TCLK0/WKUP15_1") (pintype "bidirectional"))
    )
    (net (code "69") (name "/GPIO_P_1") (class "Default")
      (node (ref "U3") (pin "6") (pinfunction "PA13/TXD1/PWMH2_6") (pintype "bidirectional"))
    )
    (net (code "70") (name "/GPIO_P_2") (class "Default")
      (node (ref "U3") (pin "8") (pinfunction "PA15/CTS1/TF/WKUP8_8") (pintype "bidirectional"))
    )
    (net (code "71") (name "/GPIO_P_3") (class "Default")
      (node (ref "U3") (pin "5") (pinfunction "PA12/RXD1/PWML1/WKUP7_5") (pintype "bidirectional"))
    )
    (net (code "72") (name "/GPIO_P_4") (class "Default")
      (node (ref "U3") (pin "2") (pinfunction "PA9/UTXD/PWMH3_2") (pintype "bidirectional"))
    )
    (net (code "73") (name "/GPIO_P_5") (class "Default")
      (node (ref "U3") (pin "7") (pinfunction "PA14/RTS1/TK_7") (pintype "bidirectional"))
    )
    (net (code "74") (name "/HOLD#") (class "Default")
      (node (ref "TP30") (pin "1") (pinfunction "1_1") (pintype "passive"))
      (node (ref "U3") (pin "103") (pinfunction "PC30/A9/TCLK7_103") (pintype "bidirectional"))
      (node (ref "U9") (pin "7") (pinfunction "HOLD#_7") (pintype "passive"))
    )
    (net (code "75") (name "/I2C_SCL") (class "Default")
      (node (ref "P6") (pin "5") (pinfunction "5_5") (pintype "passive"))
      (node (ref "R42") (pin "2") (pinfunction "2_2") (pintype "passive"))
      (node (ref "U3") (pin "70") (pinfunction "PA18/TWCK0/A20/WKUP9_70") (pintype "bidirectional"))
    )
    (net (code "76") (name "/I2C_SDA") (class "Default")
      (node (ref "P6") (pin "6") (pinfunction "6_6") (pintype "passive"))
      (node (ref "R43") (pin "2") (pinfunction "2_2") (pintype "passive"))
      (node (ref "U3") (pin "9") (pinfunction "PA17/TWD0/SPCK0_9") (pintype "bidirectional"))
    )
    (net (code "78") (name "/MAX_ES1") (class "Default")
      (node (ref "DA1") (pin "2") (pinfunction "2_2") (pintype "passive"))
      (node (ref "U3") (pin "76") (pinfunction "PB15/CANRX1/PWMH3/DAC0/WKUP12_76") (pintype "bidirectional"))
    )
    (net (code "79") (name "/MAX_ES2") (class "Default")
      (node (ref "DA2") (pin "2") (pinfunction "2_2") (pintype "passive"))
      (node (ref "U3") (pin "22") (pinfunction "PD9/A22/NANDCLE/TCLK8_22") (pintype "bidirectional"))
    )
    (net (code "80") (name "/MAX_ES3") (class "Default")
      (node (ref "DA3") (pin "2") (pinfunction "2_2") (pintype "passive"))
      (node (ref "U3") (pin "78") (pinfunction "PA16/SPCK1/TD/AD7_78") (pintype "bidirectional"))
    )
    (net (code "82") (name "/MCCDz") (class "Default")
      (node (ref "R34") (pin "2") (pinfunction "2_2") (pintype "passive"))
      (node (ref "SD") (pin "3") (pinfunction "CMD_3") (pintype "passive"))
      (node (ref "U3") (pin "72") (pinfunction "PA20/MCCDA/PWML2_72") (pintype "bidirectional"))
    )
    (net (code "83") (name "/MCCK") (class "Default")
      (node (ref "SD") (pin "5") (pinfunction "CLK_5") (pintype "passive"))
      (node (ref "U3") (pin "71") (pinfunction "PA19/MCCK/PWMH1_71") (pintype "bidirectional"))
    )
    (net (code "84") (name "/MCDz0") (class "Default")
      (node (ref "R35") (pin "2") (pinfunction "2_2") (pintype "passive"))
      (node (ref "SD") (pin "7") (pinfunction "DAT0_7") (pintype "passive"))
      (node (ref "U3") (pin "107") (pinfunction "PA21/MCDA0/PWML0_107") (pintype "bidirectional"))
    )
    (net (code "85") (name "/MCDz1") (class "Default")
      (node (ref "R40") (pin "2") (pinfunction "2_2") (pintype "passive"))
      (node (ref "SD") (pin "8") (pinfunction "DAT1_8") (pintype "passive"))
      (node (ref "U3") (pin "81") (pinfunction "PA22/MCDA1/TCLK3/AD4_81") (pintype "bidirectional"))
    )
    (net (code "86") (name "/MCDz2") (class "Default")
      (node (ref "R29") (pin "1") (pinfunction "1_1") (pintype "passive"))
      (node (ref "SD") (pin "1") (pinfunction "DAT2_1") (pintype "passive"))
      (node (ref "U3") (pin "80") (pinfunction "PA23/MCDA2/TCLK4/AD5_80") (pintype "bidirectional"))
    )
    (net (code "87") (name "/MCDz3") (class "Default")
      (node (ref "R28") (pin "1") (pinfunction "1_1") (pintype "passive"))
      (node (ref "SD") (pin "2") (pinfunction "CD/DAT3_2") (pintype "passive"))
      (node (ref "U3") (pin "79") (pinfunction "PA24/MCDA3/PCK1/AD6_79") (pintype "bidirectional"))
    )
    (net (code "89") (name "/MIN_ES1") (class "Default")
      (node (ref "DA1") (pin "1") (pinfunction "1_1") (pintype "passive"))
      (node (ref "U3") (pin "77") (pinfunction "PB16/TCLK5/PWML0/DAC1_77") (pintype "bidirectional"))
    )
    (net (code "90") (name "/MIN_ES2") (class "Default")
      (node (ref "DA2") (pin "1") (pinfunction "1_1") (pintype "passive"))
      (node (ref "U3") (pin "19") (pinfunction "PD6/A16/BA0/PWMFI2_19") (pintype "bidirectional"))
    )
    (net (code "91") (name "/MIN_ES3") (class "Default")
      (node (ref "DA3") (pin "1") (pinfunction "1_1") (pintype "passive"))
      (node (ref "U3") (pin "100") (pinfunction "PC18/NWR0/NWE/PWMH6_100") (pintype "bidirectional"))
    )
    (net (code "93") (name "/MISO") (class "Default")
      (node (ref "P3") (pin "6") (pinfunction "6_6") (pintype "passive"))
      (node (ref "P6") (pin "4") (pinfunction "4_4") (pintype "passive"))
      (node (ref "TP7") (pin "1") (pinfunction "1_1") (pintype "passive"))
      (node (ref "U3") (pin "108") (pinfunction "PA25/SPI0_MISO/A18_108") (pintype "bidirectional"))
      (node (ref "U9") (pin "5") (pinfunction "SI/IO0_5") (pintype "passive"))
    )
    (net (code "95") (name "/MOD0E1") (class "Default")
      (node (ref "U3") (pin "84") (pinfunction "PA3/TIOB1/PWMFI1/AD1/WKUP1_84") (pintype "bidirectional"))
    )
    (net (code "96") (name "/MOD0E2") (class "Default")
      (node (ref "U3") (pin "135") (pinfunction "PC24/A3/PWML7_135") (pintype "bidirectional"))
    )
    (net (code "97") (name "/MOD0E3") (class "Default")
      (node (ref "U3") (pin "113") (pinfunction "PB0/ETXCK/EREFCK_113") (pintype "bidirectional"))
    )
    (net (code "98") (name "/MOD0E4") (class "Default")
      (node (ref "U3") (pin "120") (pinfunction "PB5/ERX0_120") (pintype "bidirectional"))
    )
    (net (code "100") (name "/MOD0E_Z") (class "Default")
      (node (ref "U3") (pin "96") (pinfunction "PC14/D12/ERXCK_96") (pintype "bidirectional"))
    )
    (net (code "102") (name "/MOD1E1") (class "Default")
      (node (ref "U3") (pin "83") (pinfunction "PA4/TCLK1/NWAIT/AD2_83") (pintype "bidirectional"))
    )
    (net (code "103") (name "/MOD1E2") (class "Default")
      (node (ref "U3") (pin "140") (pinfunction "PB14/CANTX1/PWMH2_140") (pintype "bidirectional"))
    )
    (net (code "104") (name "/MOD1E3") (class "Default")
      (node (ref "U3") (pin "117") (pinfunction "PC10/D8/ECRS_117") (pintype "bidirectional"))
    )
    (net (code "105") (name "/MOD1E4") (class "Default")
      (node (ref "U3") (pin "119") (pinfunction "PB4/ECRSDV/ERXDV_119") (pintype "bidirectional"))
    )
    (net (code "107") (name "/MOD1E_Z") (class "Default")
      (node (ref "U3") (pin "95") (pinfunction "PC13/D11/ECOL_95") (pintype "bidirectional"))
    )
    (net (code "109") (name "/MOD2E1") (class "Default")
      (node (ref "U3") (pin "82") (pinfunction "PA6/TIOB2/NCS0/AD3_82") (pintype "bidirectional"))
    )
    (net (code "110") (name "/MOD2E2") (class "Default")
      (node (ref "U3") (pin "141") (pinfunction "PB22/RTS2/PCK0_141") (pintype "bidirectional"))
    )
    (net (code "111") (name "/MOD2E3") (class "Default")
      (node (ref "U3") (pin "131") (pinfunction "PC20/NANDWE/PWMH4_131") (pintype "bidirectional"))
    )
    (net (code "112") (name "/MOD2E4") (class "Default")
      (node (ref "U3") (pin "118") (pinfunction "PB3/ETX1_118") (pintype "bidirectional"))
    )
    (net (code "114") (name "/MOD2E_Z") (class "Default")
      (node (ref "U3") (pin "94") (pinfunction "PC12/D10/ERX3_94") (pintype "bidirectional"))
    )
    (net (code "115") (name "/MODE0_EXP1") (class "Default")
      (node (ref "P5") (pin "7") (pinfunction "7_7") (pintype "passive"))
      (node (ref "U3") (pin "27") (pinfunction "PA8/URXD/PWMH0/WKUP4_27") (pintype "bidirectional"))
    )
    (net (code "116") (name "/MODE0_EXP2") (class "Default")
      (node (ref "P5") (pin "5") (pinfunction "5_5") (pintype "passive"))
      (node (ref "U3") (pin "26") (pinfunction "PA7/TCLK2/NCS1/WKUP3_26") (pintype "bidirectional"))
    )
    (net (code "117") (name "/MODE1_EXP1") (class "Default")
      (node (ref "P5") (pin "3") (pinfunction "3_3") (pintype "passive"))
      (node (ref "U3") (pin "25") (pinfunction "PA5/TIOA2/PWMFI0/WKUP2_25") (pintype "bidirectional"))
    )
    (net (code "118") (name "/MODE1_EXP2") (class "Default")
      (node (ref "P5") (pin "1") (pinfunction "1_1") (pintype "passive"))
      (node (ref "U3") (pin "24") (pinfunction "PA1/CANRX0/PCK0/WKUP0_24") (pintype "bidirectional"))
    )
    (net (code "119") (name "/MODE2_EXP1") (class "Default")
      (node (ref "P5") (pin "8") (pinfunction "8_8") (pintype "passive"))
      (node (ref "U3") (pin "23") (pinfunction "PA0/CANTX0/PWML3_23") (pintype "bidirectional"))
    )
    (net (code "120") (name "/MODE2_EXP2") (class "Default")
      (node (ref "P5") (pin "6") (pinfunction "6_6") (pintype "passive"))
      (node (ref "U3") (pin "14") (pinfunction "PD1/A11/MCDA5_14") (pintype "bidirectional"))
    )
    (net (code "121") (name "/MOSI") (class "Default")
      (node (ref "P3") (pin "1") (pinfunction "1_1") (pintype "passive"))
      (node (ref "P6") (pin "1") (pinfunction "1_1") (pintype "passive"))
      (node (ref "TP8") (pin "1") (pinfunction "1_1") (pintype "passive"))
      (node (ref "U3") (pin "109") (pinfunction "PA26/SPI0_MOSI/A19_109") (pintype "bidirectional"))
      (node (ref "U9") (pin "2") (pinfunction "SO_2") (pintype "passive"))
    )
    (net (code "122") (name "/NRST") (class "Default")
      (node (ref "U3") (pin "69") (pinfunction "NRST_69") (pintype "bidirectional"))
    )
    (net (code "125") (name "/REF1") (class "Default")
      (node (ref "U3") (pin "139") (pinfunction "PC28/A7/TIOA7_139") (pintype "bidirectional"))
    )
    (net (code "126") (name "/REF2") (class "Default")
      (node (ref "U3") (pin "102") (pinfunction "PC29/A8/TIOB7_102") (pintype "bidirectional"))
    )
    (net (code "127") (name "/REF3") (class "Default")
      (node (ref "U3") (pin "136") (pinfunction "PC25/A4/TIOA6_136") (pintype "bidirectional"))
    )
    (net (code "128") (name "/REF4") (class "Default")
      (node (ref "U3") (pin "137") (pinfunction "PC26/A5/TIOB6_137") (pintype "bidirectional"))
    )
    (net (code "130") (name "/REF_EXP1") (class "Default")
      (node (ref "P5") (pin "4") (pinfunction "4_4") (pintype "passive"))
      (node (ref "U3") (pin "20") (pinfunction "PD7/A17/BA1/TIOA8_20") (pintype "bidirectional"))
    )
    (net (code "131") (name "/REF_EXP2") (class "Default")
      (node (ref "P5") (pin "2") (pinfunction "2_2") (pintype "passive"))
      (node (ref "U3") (pin "21") (pinfunction "PD8/A21/NANDALE/TIOB8_21") (pintype "bidirectional"))
    )
    (net (code "132") (name "/REF_Z") (class "Default")
      (node (ref "U3") (pin "144") (pinfunction "PB25/RTS0/TIOA0_144") (pintype "bidirectional"))
    )
    (net (code "133") (name "/RESET") (class "Default")
      (node (ref "C63") (pin "2") (pinfunction "2_2") (pintype "passive"))
      (node (ref "J2") (pin "10") (pinfunction "10_10") (pintype "passive"))
      (node (ref "P3") (pin "8") (pinfunction "8_8") (pintype "passive"))
      (node (ref "R21") (pin "1") (pinfunction "1_1") (pintype "passive"))
      (node (ref "S1") (pin "1") (pinfunction "P_1") (pintype "passive"))
      (node (ref "TP58") (pin "1") (pinfunction "1_1") (pintype "passive"))
      (node (ref "U3") (pin "47") (pinfunction "NRSTB_47") (pintype "input"))
    )
    (net (code "134") (name "/RRD1") (class "Default")
      (node (ref "P3") (pin "3") (pinfunction "3_3") (pintype "passive"))
      (node (ref "U3") (pin "127") (pinfunction "PB9/EMDIO_127") (pintype "bidirectional"))
    )
    (net (code "135") (name "/RRD2") (class "Default")
      (node (ref "P3") (pin "5") (pinfunction "5_5") (pintype "passive"))
      (node (ref "U3") (pin "128") (pinfunction "PB10/UOTGVBOF/A18_128") (pintype "bidirectional"))
    )
    (net (code "136") (name "/RRD3") (class "Default")
      (node (ref "P3") (pin "7") (pinfunction "7_7") (pintype "passive"))
      (node (ref "U3") (pin "129") (pinfunction "PB11/UOTGID/A19_129") (pintype "bidirectional"))
    )
    (net (code "137") (name "/RXD0") (class "Default")
      (node (ref "P6") (pin "8") (pinfunction "8_8") (pintype "passive"))
      (node (ref "U3") (pin "3") (pinfunction "PA10/RXD0/DATRG/WKUP5_3") (pintype "bidirectional"))
    )
    (net (code "138") (name "/RXD1") (class "Default")
      (node (ref "U3") (pin "18") (pinfunction "PD5/A15/RXD3_18") (pintype "bidirectional"))
    )
    (net (code "139") (name "/R_N") (class "Default")
      (node (ref "DA4") (pin "1") (pinfunction "1_1") (pintype "passive"))
      (node (ref "J1") (pin "2") (pinfunction "DM_2") (pintype "passive"))
      (node (ref "R18") (pin "2") (pinfunction "2_2") (pintype "passive"))
      (node (ref "TP56") (pin "1") (pinfunction "1_1") (pintype "passive"))
    )
    (net (code "140") (name "/R_P") (class "Default")
      (node (ref "DA4") (pin "2") (pinfunction "2_2") (pintype "passive"))
      (node (ref "J1") (pin "3") (pinfunction "DP_3") (pintype "passive"))
      (node (ref "R20") (pin "2") (pinfunction "2_2") (pintype "passive"))
      (node (ref "TP57") (pin "1") (pinfunction "1_1") (pintype "passive"))
    )
    (net (code "141") (name "/SCLK") (class "Default")
      (node (ref "P3") (pin "2") (pinfunction "2_2") (pintype "passive"))
      (node (ref "P6") (pin "2") (pinfunction "2_2") (pintype "passive"))
      (node (ref "TP6") (pin "1") (pinfunction "1_1") (pintype "passive"))
      (node (ref "U3") (pin "110") (pinfunction "PA27/SPI0_SPCK/A20/WKUP10_110") (pintype "bidirectional"))
      (node (ref "U9") (pin "6") (pinfunction "SCK_6") (pintype "passive"))
    )
    (net (code "142") (name "/SHDN") (class "Default")
      (node (ref "U3") (pin "50") (pinfunction "SHDN_50") (pintype "output"))
    )
    (net (code "143") (name "/SPIFLASH_CS") (class "Default")
      (node (ref "TP28") (pin "1") (pinfunction "1_1") (pintype "passive"))
      (node (ref "U3") (pin "111") (pinfunction "PA28/SPI0_NPCS0/PCK2/WKUP11_111") (pintype "bidirectional"))
      (node (ref "U9") (pin "1") (pinfunction "CS_1") (pintype "passive"))
    )
    (net (code "144") (name "/STATUS_A") (class "Default")
      (node (ref "U3") (pin "142") (pinfunction "PB23/CTS2/SPI0_NPCS3/WKUP14_142") (pintype "bidirectional"))
    )
    (net (code "145") (name "/STATUS_B") (class "Default")
      (node (ref "U3") (pin "143") (pinfunction "PB24/SCK2/NCS2_143") (pintype "bidirectional"))
    )
    (net (code "147") (name "/STEP1") (class "Default")
      (node (ref "U3") (pin "85") (pinfunction "PA2/TIOA1/NANDRDY/AD0_85") (pintype "bidirectional"))
    )
    (net (code "148") (name "/STEP2") (class "Default")
      (node (ref "U3") (pin "134") (pinfunction "PC23/A2/PWML6_134") (pintype "bidirectional"))
    )
    (net (code "149") (name "/STEP3") (class "Default")
      (node (ref "U3") (pin "114") (pinfunction "PB1/ETXEN_114") (pintype "bidirectional"))
    )
    (net (code "150") (name "/STEP4") (class "Default")
      (node (ref "U3") (pin "121") (pinfunction "PB6/ERX1_121") (pintype "bidirectional"))
    )
    (net (code "152") (name "/STEP_EXP1") (class "Default")
      (node (ref "P4") (pin "8") (pinfunction "8_8") (pintype "passive"))
      (node (ref "U3") (pin "68") (pinfunction "PB27/NCS3/TIOB0_68") (pintype "bidirectional"))
    )
    (net (code "153") (name "/STEP_EXP2") (class "Default")
      (node (ref "P4") (pin "7") (pinfunction "7_7") (pintype "passive"))
      (node (ref "U3") (pin "13") (pinfunction "PD0/A10/MCDA4_13") (pintype "bidirectional"))
    )
    (net (code "154") (name "/STEP_Z") (class "Default")
      (node (ref "U3") (pin "97") (pinfunction "PC15/D13/ETX2_97") (pintype "bidirectional"))
    )
    (net (code "155") (name "/TCK{slash}SWDCLK") (class "Default")
      (node (ref "J2") (pin "4") (pinfunction "4_4") (pintype "passive"))
      (node (ref "TP60") (pin "1") (pinfunction "1_1") (pintype "passive"))
      (node (ref "U3") (pin "28") (pinfunction "PB28/TCK/SWCLK_28") (pintype "bidirectional"))
    )
    (net (code "156") (name "/TC_CS2") (class "Default")
      (node (ref "U3") (pin "112") (pinfunction "PA29/SPI0_NPCS1/NRD_112") (pintype "bidirectional"))
    )
    (net (code "157") (name "/TDI") (class "Default")
      (node (ref "J2") (pin "8") (pinfunction "8_8") (pintype "passive"))
      (node (ref "TP62") (pin "1") (pinfunction "1_1") (pintype "passive"))
      (node (ref "U3") (pin "29") (pinfunction "PB29/TDI_29") (pintype "bidirectional"))
    )
    (net (code "158") (name "/TDO{slash}SWO") (class "Default")
      (node (ref "J2") (pin "6") (pinfunction "6_6") (pintype "passive"))
      (node (ref "TP61") (pin "1") (pinfunction "1_1") (pintype "passive"))
      (node (ref "U3") (pin "30") (pinfunction "PB30/TDO/TRACESWO_30") (pintype "bidirectional"))
    )
    (net (code "160") (name "/THERM_AN1") (class "Default")
      (node (ref "U3") (pin "88") (pinfunction "PB17/RF/PWML1/AD10_88") (pintype "bidirectional"))
    )
    (net (code "161") (name "/THERM_AN2") (class "Default")
      (node (ref "U3") (pin "89") (pinfunction "PB18/RD/PWML2/AD11_89") (pintype "bidirectional"))
    )
    (net (code "162") (name "/THERM_AN3") (class "Default")
      (node (ref "U3") (pin "90") (pinfunction "PB19/RK/PWML3/AD12_90") (pintype "bidirectional"))
    )
    (net (code "163") (name "/THERM_AN4") (class "Default")
      (node (ref "U3") (pin "91") (pinfunction "PB20/TXD2/SPI0_NPCS1/AD13_91") (pintype "bidirectional"))
    )
    (net (code "165") (name "/TMS{slash}SWDIO") (class "Default")
      (node (ref "J2") (pin "2") (pinfunction "2_2") (pintype "passive"))
      (node (ref "TP59") (pin "1") (pinfunction "1_1") (pintype "passive"))
      (node (ref "U3") (pin "31") (pinfunction "PB31/TMS/SWDIO_31") (pintype "bidirectional"))
    )
    (net (code "166") (name "/TXD0") (class "Default")
      (node (ref "P6") (pin "7") (pinfunction "7_7") (pintype "passive"))
      (node (ref "U3") (pin "4") (pinfunction "PA11/TXD0/ADTRG/WKUP6_4") (pintype "bidirectional"))
    )
    (net (code "167") (name "/TXD1") (class "Default")
      (node (ref "U3") (pin "17") (pinfunction "PD4/A14/TXD3_17") (pintype "bidirectional"))
    )
    (net (code "168") (name "/UD_N") (class "Default")
      (node (ref "R18") (pin "1") (pinfunction "1_1") (pintype "passive"))
      (node (ref "U6") (pin "6") (pinfunction "UD-_1_6") (pintype "passive"))
    )
    (net (code "169") (name "/UD_P") (class "Default")
      (node (ref "R20") (pin "1") (pinfunction "1_1") (pintype "passive"))
      (node (ref "U6") (pin "7") (pinfunction "UD+_1_7") (pintype "passive"))
    )
    (net (code "170") (name "/UI_N") (class "Default")
      (node (ref "R16") (pin "2") (pinfunction "2_2") (pintype "passive"))
      (node (ref "U6") (pin "11") (pinfunction "UD-_2_11") (pintype "passive"))
    )
    (net (code "171") (name "/UI_P") (class "Default")
      (node (ref "R15") (pin "2") (pinfunction "2_2") (pintype "passive"))
      (node (ref "U6") (pin "10") (pinfunction "UD+_2_10") (pintype "passive"))
    )
    (net (code "172") (name "/UMCU_N") (class "Default")
      (node (ref "R16") (pin "1") (pinfunction "1_1") (pintype "passive"))
      (node (ref "R22") (pin "2") (pinfunction "2_2") (pintype "passive"))
      (node (ref "U3") (pin "38") (pinfunction "DHSDM_38") (pintype "bidirectional"))
    )
    (net (code "173") (name "/UMCU_P") (class "Default")
      (node (ref "R15") (pin "1") (pinfunction "1_1") (pintype "passive"))
      (node (ref "R5") (pin "2") (pinfunction "2_2") (pintype "passive"))
      (node (ref "U3") (pin "37") (pinfunction "DHSDP_37") (pintype "bidirectional"))
    )
    (net (code "174") (name "/USB_RX") (class "Default")
      (node (ref "R25") (pin "1") (pinfunction "1_1") (pintype "passive"))
      (node (ref "U3") (pin "15") (pinfunction "PD2/A12/MCDA6_15") (pintype "bidirectional"))
    )
    (net (code "175") (name "/USB_TX") (class "Default")
      (node (ref "R26") (pin "1") (pinfunction "1_1") (pintype "passive"))
      (node (ref "U3") (pin "16") (pinfunction "PD3/A13/MCDA7_16") (pintype "bidirectional"))
    )
    (net (code "176") (name "/VBUS") (class "Default")
      (node (ref "C57") (pin "1") (pinfunction "1_1") (pintype "passive"))
      (node (ref "U3") (pin "39") (pinfunction "VBUS_39") (pintype "bidirectional"))
      (node (ref "U6") (pin "16") (pinfunction "VBUS2_16") (pintype "passive"))
    )
    (net (code "177") (name "/VDD1") (class "Default")
      (node (ref "C59") (pin "1") (pinfunction "1_1") (pintype "passive"))
      (node (ref "U6") (pin "3") (pinfunction "VDD1_3") (pintype "passive"))
      (node (ref "U6") (pin "4") (pinfunction "PDEN_4") (pintype "passive"))
      (node (ref "U6") (pin "5") (pinfunction "SPU_5") (pintype "passive"))
    )
    (net (code "178") (name "/VDDANA") (class "Default")
      (node (ref "C13") (pin "2") (pinfunction "2_2") (pintype "passive"))
      (node (ref "C27") (pin "1") (pinfunction "1_1") (pintype "passive"))
      (node (ref "FB6") (pin "2") (pinfunction "2_2") (pintype "passive"))
      (node (ref "U3") (pin "73") (pinfunction "VDDANA_73") (pintype "power_in"))
    )
    (net (code "179") (name "/VDDBU") (class "Default")
      (node (ref "C28") (pin "2") (pinfunction "2_2") (pintype "passive"))
      (node (ref "C53") (pin "1") (pinfunction "1_1") (pintype "passive"))
      (node (ref "FB7") (pin "2") (pinfunction "2_2") (pintype "passive"))
      (node (ref "U3") (pin "52") (pinfunction "VDDBU_52") (pintype "power_in"))
    )
    (net (code "180") (name "/VDDIN") (class "Default")
      (node (ref "C54") (pin "1") (pinfunction "1_1") (pintype "passive"))
      (node (ref "C55") (pin "2") (pinfunction "2_2") (pintype "passive"))
      (node (ref "FB5") (pin "2") (pinfunction "2_2") (pintype "passive"))
      (node (ref "U3") (pin "57") (pinfunction "VDDIN_57") (pintype "power_in"))
    )
    (net (code "181") (name "/VDDOUT") (class "Default")
      (node (ref "C23") (pin "1") (pinfunction "1_1") (pintype "passive"))
      (node (ref "C36") (pin "2") (pinfunction "2_2") (pintype "passive"))
      (node (ref "C37") (pin "1") (pinfunction "1_1") (pintype "passive"))
      (node (ref "C38") (pin "1") (pinfunction "1_1") (pintype "passive"))
      (node (ref "C39") (pin "1") (pinfunction "1_1") (pintype "passive"))
      (node (ref "C41") (pin "1") (pinfunction "1_1") (pintype "passive"))
      (node (ref "C42") (pin "1") (pinfunction "1_1") (pintype "passive"))
      (node (ref "FB4") (pin "1") (pinfunction "1_1") (pintype "passive"))
      (node (ref "U3") (pin "10") (pinfunction "VDDCORE_10") (pintype "power_in"))
      (node (ref "U3") (pin "104") (pinfunction "VDDCORE_104") (pintype "power_in"))
      (node (ref "U3") (pin "124") (pinfunction "VDDCORE_124") (pintype "power_in"))
      (node (ref "U3") (pin "45") (pinfunction "VDDCORE_45") (pintype "power_in"))
      (node (ref "U3") (pin "56") (pinfunction "VDDOUT_56") (pintype "power_in"))
      (node (ref "U3") (pin "61") (pinfunction "VDDCORE_61") (pintype "power_in"))
    )
    (net (code "182") (name "/VDDPLL") (class "Default")
      (node (ref "C32") (pin "2") (pinfunction "2_2") (pintype "passive"))
      (node (ref "C33") (pin "1") (pinfunction "1_1") (pintype "passive"))
      (node (ref "FB4") (pin "2") (pinfunction "2_2") (pintype "passive"))
      (node (ref "U3") (pin "34") (pinfunction "VDDPLL_34") (pintype "power_in"))
    )
    (net (code "183") (name "/VDDUTMI") (class "Default")
      (node (ref "C60") (pin "2") (pinfunction "2_2") (pintype "passive"))
      (node (ref "C61") (pin "1") (pinfunction "1_1") (pintype "passive"))
      (node (ref "FB8") (pin "2") (pinfunction "2_2") (pintype "passive"))
      (node (ref "U3") (pin "41") (pinfunction "VDDUTMI_41") (pintype "power_in"))
    )
    (net (code "184") (name "/WP#") (class "Default")
      (node (ref "TP29") (pin "1") (pinfunction "1_1") (pintype "passive"))
      (node (ref "U3") (pin "101") (pinfunction "PC19/NANDOE/PWMH5_101") (pintype "bidirectional"))
      (node (ref "U9") (pin "3") (pinfunction "WP#_3") (pintype "passive"))
    )
    (net (code "185") (name "/XIN32") (class "Default")
      (node (ref "U3") (pin "48") (pinfunction "XIN32_48") (pintype "bidirectional"))
    )
    (net (code "186") (name "/XOUT32") (class "Default")
      (node (ref "U3") (pin "49") (pinfunction "XOUT32_49") (pintype "passive"))
    )
    (net (code "187") (name "3.3VCC") (class "Default")
      (node (ref "C34") (pin "1") (pinfunction "1_1") (pintype "passive"))
      (node (ref "C4") (pin "1") (pinfunction "1_1") (pintype "passive"))
      (node (ref "C45") (pin "1") (pinfunction "1_1") (pintype "passive"))
      (node (ref "C46") (pin "1") (pinfunction "1_1") (pintype "passive"))
      (node (ref "C47") (pin "1") (pinfunction "1_1") (pintype "passive"))
      (node (ref "C48") (pin "1") (pinfunction "1_1") (pintype "passive"))
      (node (ref "C56") (pin "1") (pinfunction "1_1") (pintype "passive"))
      (node (ref "C64") (pin "1") (pinfunction "1_1") (pintype "passive"))
      (node (ref "C74") (pin "1") (pinfunction "1_1") (pintype "passive"))
      (node (ref "FB5") (pin "1") (pinfunction "1_1") (pintype "passive"))
      (node (ref "FB6") (pin "1") (pinfunction "1_1") (pintype "passive"))
      (node (ref "FB7") (pin "1") (pinfunction "1_1") (pintype "passive"))
      (node (ref "FB8") (pin "1") (pinfunction "1_1") (pintype "passive"))
      (node (ref "FB9") (pin "1") (pinfunction "1_1") (pintype "passive"))
      (node (ref "J2") (pin "1") (pinfunction "1_1") (pintype "passive"))
      (node (ref "P1") (pin "1") (pinfunction "1_1") (pintype "passive"))
      (node (ref "P3") (pin "10") (pinfunction "10_10") (pintype "passive"))
      (node (ref "P5") (pin "10") (pinfunction "10_10") (pintype "passive"))
      (node (ref "P6") (pin "10") (pinfunction "10_10") (pintype "passive"))
      (node (ref "R21") (pin "2") (pinfunction "2_2") (pintype "passive"))
      (node (ref "R28") (pin "2") (pinfunction "2_2") (pintype "passive"))
      (node (ref "R29") (pin "2") (pinfunction "2_2") (pintype "passive"))
      (node (ref "R34") (pin "1") (pinfunction "1_1") (pintype "passive"))
      (node (ref "R35") (pin "1") (pinfunction "1_1") (pintype "passive"))
      (node (ref "R40") (pin "1") (pinfunction "1_1") (pintype "passive"))
      (node (ref "R42") (pin "1") (pinfunction "1_1") (pintype "passive"))
      (node (ref "R43") (pin "1") (pinfunction "1_1") (pintype "passive"))
      (node (ref "R6") (pin "2") (pinfunction "2_2") (pintype "passive"))
      (node (ref "SD") (pin "4") (pinfunction "VDD_4") (pintype "passive"))
      (node (ref "U3") (pin "105") (pinfunction "VDDIO_105") (pintype "power_in"))
      (node (ref "U3") (pin "11") (pinfunction "VDDIO_11") (pintype "power_in"))
      (node (ref "U3") (pin "125") (pinfunction "VDDIO_125") (pintype "power_in"))
      (node (ref "U3") (pin "62") (pinfunction "VDDIO_62") (pintype "power_in"))
      (node (ref "U6") (pin "12") (pinfunction "PIN_12") (pintype "passive"))
      (node (ref "U6") (pin "13") (pinfunction "SPD_13") (pintype "passive"))
      (node (ref "U6") (pin "14") (pinfunction "VDD2_14") (pintype "passive"))
      (node (ref "U9") (pin "8") (pinfunction "VCC_8") (pintype "passive"))
    )
    (net (code "188") (name "FGND") (class "Default")
      (node (ref "D8") (pin "C") (pinfunction "C_C") (pintype "power_in"))
      (node (ref "D9") (pin "C") (pinfunction "C_C") (pintype "power_in"))
      (node (ref "S1") (pin "3") (pinfunction "3_3") (pintype "power_in"))
      (node (ref "S1") (pin "4") (pinfunction "4_4") (pintype "power_in"))
    )
    (net (code "189") (name "GND") (class "Default")
      (node (ref "C13") (pin "1") (pinfunction "1_1") (pintype "passive"))
      (node (ref "C19") (pin "2") (pinfunction "2_2") (pintype "passive"))
      (node (ref "C23") (pin "2") (pinfunction "2_2") (pintype "passive"))
      (node (ref "C27") (pin "2") (pinfunction "2_2") (pintype "passive"))
      (node (ref "C28") (pin "1") (pinfunction "1_1") (pintype "passive"))
      (node (ref "C29") (pin "1") (pinfunction "1_1") (pintype "passive"))
      (node (ref "C32") (pin "1") (pinfunction "1_1") (pintype "passive"))
      (node (ref "C33") (pin "2") (pinfunction "2_2") (pintype "passive"))
      (node (ref "C34") (pin "2") (pinfunction "2_2") (pintype "passive"))
      (node (ref "C36") (pin "1") (pinfunction "1_1") (pintype "passive"))
      (node (ref "C37") (pin "2") (pinfunction "2_2") (pintype "passive"))
      (node (ref "C38") (pin "2") (pinfunction "2_2") (pintype "passive"))
      (node (ref "C39") (pin "2") (pinfunction "2_2") (pintype "passive"))
      (node (ref "C4") (pin "2") (pinfunction "2_2") (pintype "passive"))
      (node (ref "C41") (pin "2") (pinfunction "2_2") (pintype "passive"))
      (node (ref "C42") (pin "2") (pinfunction "2_2") (pintype "passive"))
      (node (ref "C43") (pin "1") (pinfunction "1_1") (pintype "passive"))
      (node (ref "C44") (pin "1") (pinfunction "1_1") (pintype "passive"))
      (node (ref "C45") (pin "2") (pinfunction "2_2") (pintype "passive"))
      (node (ref "C46") (pin "2") (pinfunction "2_2") (pintype "passive"))
      (node (ref "C47") (pin "2") (pinfunction "2_2") (pintype "passive"))
      (node (ref "C48") (pin "2") (pinfunction "2_2") (pintype "passive"))
      (node (ref "C53") (pin "2") (pinfunction "2_2") (pintype "passive"))
      (node (ref "C54") (pin "2") (pinfunction "2_2") (pintype "passive"))
      (node (ref "C55") (pin "1") (pinfunction "1_1") (pintype "passive"))
      (node (ref "C56") (pin "2") (pinfunction "2_2") (pintype "passive"))
      (node (ref "C57") (pin "2") (pinfunction "2_2") (pintype "passive"))
      (node (ref "C60") (pin "1") (pinfunction "1_1") (pintype "passive"))
      (node (ref "C61") (pin "2") (pinfunction "2_2") (pintype "passive"))
      (node (ref "C63") (pin "1") (pinfunction "1_1") (pintype "passive"))
      (node (ref "C64") (pin "2") (pinfunction "2_2") (pintype "passive"))
      (node (ref "C65") (pin "2") (pinfunction "2_2") (pintype "passive"))
      (node (ref "C73") (pin "1") (pinfunction "1_1") (pintype "passive"))
      (node (ref "C74") (pin "2") (pinfunction "2_2") (pintype "passive"))
      (node (ref "D24") (pin "C") (pinfunction "C_C") (pintype "passive"))
      (node (ref "D29") (pin "C") (pinfunction "C_C") (pintype "passive"))
      (node (ref "DA1") (pin "3") (pinfunction "3_3") (pintype "passive"))
      (node (ref "DA2") (pin "3") (pinfunction "3_3") (pintype "passive"))
      (node (ref "DA3") (pin "3") (pinfunction "3_3") (pintype "passive"))
      (node (ref "GND_TP") (pin "1") (pinfunction "1_1") (pintype "passive"))
      (node (ref "J2") (pin "3") (pinfunction "3_3") (pintype "passive"))
      (node (ref "J2") (pin "5") (pinfunction "5_5") (pintype "passive"))
      (node (ref "J2") (pin "9") (pinfunction "9_9") (pintype "passive"))
      (node (ref "P3") (pin "9") (pinfunction "9_9") (pintype "passive"))
      (node (ref "P4") (pin "9") (pinfunction "9_9") (pintype "passive"))
      (node (ref "P5") (pin "9") (pinfunction "9_9") (pintype "passive"))
      (node (ref "P6") (pin "9") (pinfunction "9_9") (pintype "passive"))
      (node (ref "R23") (pin "1") (pinfunction "1_1") (pintype "passive"))
      (node (ref "R4") (pin "2") (pinfunction "2_2") (pintype "passive"))
      (node (ref "R41") (pin "1") (pinfunction "1_1") (pintype "passive"))
      (node (ref "S1") (pin "2") (pinfunction "S_2") (pintype "passive"))
      (node (ref "SD") (pin "6") (pinfunction "VSS_6") (pintype "passive"))
      (node (ref "U3") (pin "106") (pinfunction "GND_106") (pintype "power_in"))
      (node (ref "U3") (pin "12") (pinfunction "GND_12") (pintype "power_in"))
      (node (ref "U3") (pin "126") (pinfunction "GND_126") (pintype "power_in"))
      (node (ref "U3") (pin "33") (pinfunction "GNDPLL_33") (pintype "power_in"))
      (node (ref "U3") (pin "44") (pinfunction "GNDUTMI_44") (pintype "power_in"))
      (node (ref "U3") (pin "46") (pinfunction "JTAGSEL_46") (pintype "input"))
      (node (ref "U3") (pin "54") (pinfunction "GNDBU_54") (pintype "power_in"))
      (node (ref "U3") (pin "58") (pinfunction "GND_58") (pintype "power_in"))
      (node (ref "U3") (pin "74") (pinfunction "GNDANA_74") (pintype "power_in"))
      (node (ref "U6") (pin "15") (pinfunction "GND2_15") (pintype "passive"))
      (node (ref "U6") (pin "9") (pinfunction "GND2_9") (pintype "passive"))
      (node (ref "U9") (pin "4") (pinfunction "GND_4") (pintype "passive"))
    )
    (net (code "190") (name "INPUT_GND") (class "Default")
      (node (ref "C24") (pin "1") (pinfunction "1_1") (pintype "passive"))
      (node (ref "C58") (pin "2") (pinfunction "2_2") (pintype "passive"))
      (node (ref "C59") (pin "2") (pinfunction "2_2") (pintype "passive"))
      (node (ref "DA4") (pin "3") (pinfunction "3_3") (pintype "passive"))
      (node (ref "J1") (pin "4") (pinfunction "GND_4") (pintype "passive"))
      (node (ref "R24") (pin "1") (pinfunction "1_1") (pintype "passive"))
      (node (ref "U6") (pin "2") (pinfunction "GND1_2") (pintype "passive"))
      (node (ref "U6") (pin "8") (pinfunction "GND1_8") (pintype "passive"))
    )
    (net (code "191") (name "Net-(C19-Pad1)") (class "Default")
      (node (ref "C19") (pin "1") (pinfunction "1_1") (pintype "passive"))
      (node (ref "D9") (pin "A") (pinfunction "A_A") (pintype "power_in"))
      (node (ref "R41") (pin "2") (pinfunction "2_2") (pintype "passive"))
      (node (ref "SD") (pin "10") (pinfunction "GND_10") (pintype "passive"))
      (node (ref "SD") (pin "11") (pinfunction "GND_11") (pintype "passive"))
      (node (ref "SD") (pin "12") (pinfunction "GND_12") (pintype "passive"))
      (node (ref "SD") (pin "13") (pinfunction "GND_13") (pintype "passive"))
      (node (ref "SD") (pin "9") (pinfunction "GND_9") (pintype "passive"))
    )
    (net (code "192") (name "Net-(C24-Pad2)") (class "Default")
      (node (ref "C24") (pin "2") (pinfunction "2_2") (pintype "passive"))
      (node (ref "D8") (pin "A") (pinfunction "A_A") (pintype "power_in"))
      (node (ref "J1") (pin "5") (pinfunction "SHLD_5") (pintype "passive"))
      (node (ref "J1") (pin "6") (pinfunction "SHLD_6") (pintype "passive"))
      (node (ref "R24") (pin "2") (pinfunction "2_2") (pintype "passive"))
    )
    (net (code "193") (name "Net-(D24-PadA)") (class "Default")
      (node (ref "D24") (pin "A") (pinfunction "A_A") (pintype "passive"))
      (node (ref "R25") (pin "2") (pinfunction "2_2") (pintype "passive"))
    )
    (net (code "194") (name "Net-(D29-PadA)") (class "Default")
      (node (ref "D29") (pin "A") (pinfunction "A_A") (pintype "passive"))
      (node (ref "R26") (pin "2") (pinfunction "2_2") (pintype "passive"))
    )
    (net (code "195") (name "Net-(J1-VBUS)") (class "Default")
      (node (ref "C58") (pin "1") (pinfunction "1_1") (pintype "passive"))
      (node (ref "J1") (pin "1") (pinfunction "VBUS_1") (pintype "passive"))
      (node (ref "U6") (pin "1") (pinfunction "VBUS1_1") (pintype "passive"))
    )
    (net (code "196") (name "Net-(U3B-DFSDM)") (class "Default")
      (node (ref "R22") (pin "1") (pinfunction "1_1") (pintype "passive"))
      (node (ref "U3") (pin "43") (pinfunction "DFSDM_43") (pintype "bidirectional"))
    )
    (net (code "197") (name "Net-(U3B-DFSDP)") (class "Default")
      (node (ref "R5") (pin "1") (pinfunction "1_1") (pintype "passive"))
      (node (ref "U3") (pin "42") (pinfunction "DFSDP_42") (pintype "bidirectional"))
    )
    (net (code "198") (name "Net-(U3B-FWUP)") (class "Default")
      (node (ref "R6") (pin "1") (pinfunction "1_1") (pintype "passive"))
      (node (ref "U3") (pin "53") (pinfunction "FWUP_53") (pintype "input"))
    )
    (net (code "199") (name "Net-(U3B-TST)") (class "Default")
      (node (ref "R4") (pin "1") (pinfunction "1_1") (pintype "passive"))
      (node (ref "U3") (pin "51") (pinfunction "TST_51") (pintype "input"))
    )
    (net (code "200") (name "Net-(U3B-VBG)") (class "Default")
      (node (ref "C73") (pin "2") (pinfunction "2_2") (pintype "passive"))
      (node (ref "R23") (pin "2") (pinfunction "2_2") (pintype "passive"))
      (node (ref "U3") (pin "40") (pinfunction "VBG_40") (pintype "passive"))
    )
    (net (code "201") (name "Net-(U3B-XIN)") (class "Default")
      (node (ref "C43") (pin "2") (pinfunction "2_2") (pintype "passive"))
      (node (ref "U3") (pin "36") (pinfunction "XIN_36") (pintype "passive"))
      (node (ref "X2") (pin "1") (pinfunction "OSC1_1") (pintype "passive"))
    )
    (net (code "202") (name "Net-(U3B-XOUT)") (class "Default")
      (node (ref "C44") (pin "2") (pinfunction "2_2") (pintype "passive"))
      (node (ref "U3") (pin "35") (pinfunction "XOUT_35") (pintype "passive"))
      (node (ref "X2") (pin "2") (pinfunction "OSC2_2") (pintype "passive"))
    )
    (net (code "203") (name "unconnected-(J2-Pad7)") (class "Default")
      (node (ref "J2") (pin "7") (pinfunction "7_7") (pintype "passive+no_connect"))
    )
    (net (code "204") (name "unconnected-(P4-Pad1)") (class "Default")
      (node (ref "P4") (pin "1") (pinfunction "1_1") (pintype "passive"))
    )
    (net (code "205") (name "unconnected-(P4-Pad2)") (class "Default")
      (node (ref "P4") (pin "2") (pinfunction "2_2") (pintype "passive"))
    )
    (net (code "206") (name "unconnected-(U3A-PD10{slash}NWR1{slash}NBS1-Pad32)") (class "Default")
      (node (ref "U3") (pin "32") (pinfunction "PD10/NWR1/NBS1_32") (pintype "bidirectional"))
    )
  )
)
